# Module.net
KiCad netlist of a schematic drawn in Altium Designer
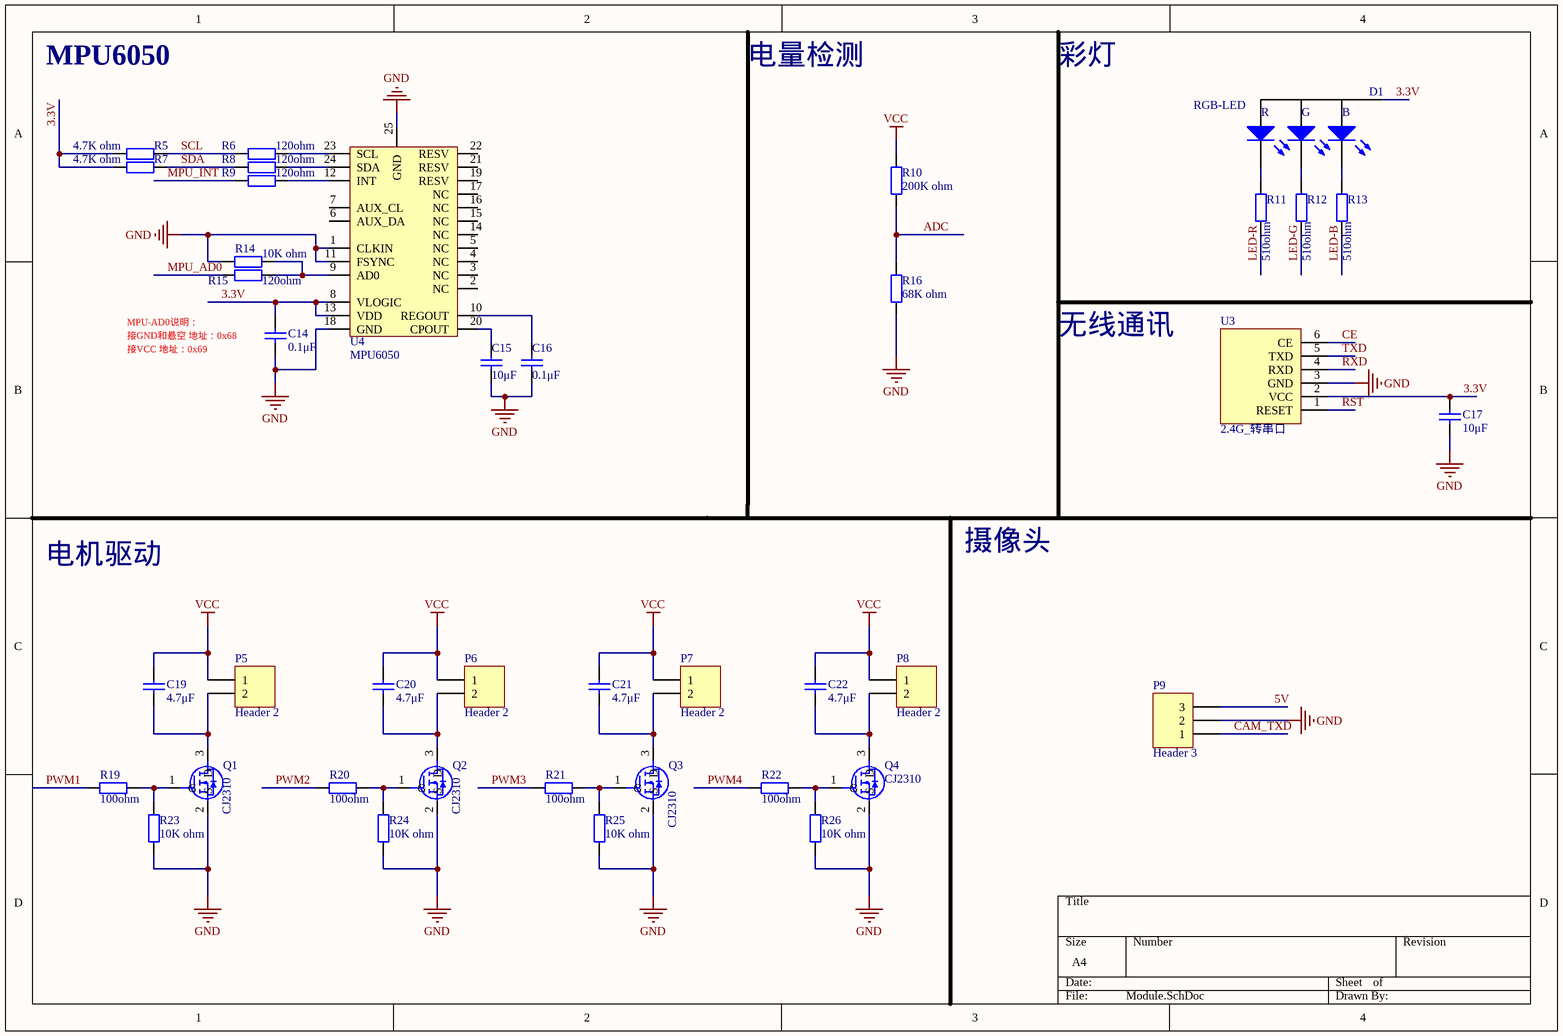
[diagram p0: Module.SchDoc]

(export (version "E")
  (design (tool "Eeschema 10.0.6"))
  (components
    (comp (ref "C14")
      (value "0.1μF")
      (footprint "0603C")
      (description "0.1μF_50V,X7R,±5%")
      (libsource (lib "Yang_Lib") (part "Cap_0.1μF_50V_0603"))
    )
    (comp (ref "C15")
      (value "10μF")
      (footprint "0603C")
      (description "10μF_35V,X5R,20%")
      (libsource (lib "Yang_Lib") (part "Cap_10μF_35V_0603"))
    )
    (comp (ref "C16")
      (value "0.1μF")
      (footprint "0603C")
      (description "0.1μF_50V,X7R,±5%")
      (libsource (lib "Yang_Lib") (part "Cap_0.1μF_50V_0603"))
    )
    (comp (ref "C17")
      (value "10μF")
      (footprint "0603C")
      (description "10μF_35V,X5R,20%")
      (libsource (lib "Yang_Lib") (part "Cap_10μF_35V_0603"))
    )
    (comp (ref "C19")
      (value "4.7μF")
      (footprint "0603C")
      (description "4.7μF_50V,±10%")
      (libsource (lib "Yang_Lib") (part "Cap_4.7μF_50V_0603"))
    )
    (comp (ref "C20")
      (value "4.7μF")
      (footprint "0603C")
      (description "4.7μF_50V,±10%")
      (libsource (lib "Yang_Lib") (part "Cap_4.7μF_50V_0603"))
    )
    (comp (ref "C21")
      (value "4.7μF")
      (footprint "0603C")
      (description "4.7μF_50V,±10%")
      (libsource (lib "Yang_Lib") (part "Cap_4.7μF_50V_0603"))
    )
    (comp (ref "C22")
      (value "4.7μF")
      (footprint "0603C")
      (description "4.7μF_50V,±10%")
      (libsource (lib "Yang_Lib") (part "Cap_4.7μF_50V_0603"))
    )
    (comp (ref "D1") (value "RGB-LED") (footprint "RGB-LED") (libsource (lib "Yang_Lib") (part "RGB-LED")))
    (comp (ref "P5")
      (value "Header 2")
      (footprint "HDR1X2")
      (description "Header, 2-Pin")
      (fields (field (name "PUBLISHER") "Altium Limited"))
      (libsource (lib "Miscellaneous Connectors") (part "Header 2"))
    )
    (comp (ref "P6")
      (value "Header 2")
      (footprint "HDR1X2")
      (description "Header, 2-Pin")
      (fields (field (name "PUBLISHER") "Altium Limited"))
      (libsource (lib "Miscellaneous Connectors") (part "Header 2"))
    )
    (comp (ref "P7")
      (value "Header 2")
      (footprint "HDR1X2")
      (description "Header, 2-Pin")
      (fields (field (name "PUBLISHER") "Altium Limited"))
      (libsource (lib "Miscellaneous Connectors") (part "Header 2"))
    )
    (comp (ref "P8")
      (value "Header 2")
      (footprint "HDR1X2")
      (description "Header, 2-Pin")
      (fields (field (name "PUBLISHER") "Altium Limited"))
      (libsource (lib "Miscellaneous Connectors") (part "Header 2"))
    )
    (comp (ref "P9")
      (value "Header 3")
      (footprint "HDR1X3")
      (description "Header, 3-Pin")
      (fields (field (name "PUBLISHER") "Altium Limited"))
      (libsource (lib "Miscellaneous Connectors") (part "Header 3"))
    )
    (comp (ref "Q1") (value "CJ2310") (footprint "SOT23-3") (libsource (lib "Yang_Lib") (part "CJ2310")))
    (comp (ref "Q2") (value "CJ2310") (footprint "SOT23-3") (libsource (lib "Yang_Lib") (part "CJ2310")))
    (comp (ref "Q3") (value "CJ2310") (footprint "SOT23-3") (libsource (lib "Yang_Lib") (part "CJ2310")))
    (comp (ref "Q4") (value "CJ2310") (footprint "SOT23-3") (libsource (lib "Yang_Lib") (part "CJ2310")))
    (comp (ref "R5")
      (value "4.7K ohm")
      (footprint "0603R")
      (description "4.7K ohm,1%")
      (libsource (lib "Yang_Lib") (part "Res_4.7K ohm_0603"))
    )
    (comp (ref "R6")
      (value "120ohm")
      (footprint "0603R")
      (description "120 ohm_5%")
      (libsource (lib "Yang_Lib") (part "Res_120ohm_0603"))
    )
    (comp (ref "R7")
      (value "4.7K ohm")
      (footprint "0603R")
      (description "4.7K ohm,1%")
      (libsource (lib "Yang_Lib") (part "Res_4.7K ohm_0603"))
    )
    (comp (ref "R8")
      (value "120ohm")
      (footprint "0603R")
      (description "120 ohm_5%")
      (libsource (lib "Yang_Lib") (part "Res_120ohm_0603"))
    )
    (comp (ref "R9")
      (value "120ohm")
      (footprint "0603R")
      (description "120 ohm_5%")
      (libsource (lib "Yang_Lib") (part "Res_120ohm_0603"))
    )
    (comp (ref "R10")
      (value "200K ohm")
      (footprint "0603R")
      (description "200K ohm,1%")
      (libsource (lib "Yang_Lib") (part "Res_200K ohm_0603"))
    )
    (comp (ref "R11")
      (value "510ohm")
      (footprint "0603R")
      (description "510 ohm,1%")
      (libsource (lib "Yang_Lib") (part "Res_510ohm_0603"))
    )
    (comp (ref "R12")
      (value "510ohm")
      (footprint "0603R")
      (description "510 ohm,1%")
      (libsource (lib "Yang_Lib") (part "Res_510ohm_0603"))
    )
    (comp (ref "R13")
      (value "510ohm")
      (footprint "0603R")
      (description "510 ohm,1%")
      (libsource (lib "Yang_Lib") (part "Res_510ohm_0603"))
    )
    (comp (ref "R14")
      (value "10K ohm")
      (footprint "0603R")
      (description "10K ohm,1%")
      (libsource (lib "") (part "Res_10K ohm_0603_1"))
    )
    (comp (ref "R15")
      (value "120ohm")
      (footprint "0603R")
      (description "120 ohm_5%")
      (libsource (lib "Yang_Lib") (part "Res_120ohm_0603"))
    )
    (comp (ref "R16")
      (value "68K ohm")
      (footprint "0603R")
      (description "68K ohm,1%")
      (libsource (lib "Yang_Lib") (part "Res_68K ohm_0603"))
    )
    (comp (ref "R19")
      (value "100ohm")
      (footprint "0603R")
      (description "100 ohm_5%")
      (libsource (lib "Yang_Lib") (part "Res_100ohm_0603"))
    )
    (comp (ref "R20")
      (value "100ohm")
      (footprint "0603R")
      (description "100 ohm_5%")
      (libsource (lib "Yang_Lib") (part "Res_100ohm_0603"))
    )
    (comp (ref "R21")
      (value "100ohm")
      (footprint "0603R")
      (description "100 ohm_5%")
      (libsource (lib "Yang_Lib") (part "Res_100ohm_0603"))
    )
    (comp (ref "R22")
      (value "100ohm")
      (footprint "0603R")
      (description "100 ohm_5%")
      (libsource (lib "Yang_Lib") (part "Res_100ohm_0603"))
    )
    (comp (ref "R23")
      (value "10K ohm")
      (footprint "0603R")
      (description "10K ohm,1%")
      (libsource (lib "Yang_Lib") (part "Res_10K ohm_0603"))
    )
    (comp (ref "R24")
      (value "10K ohm")
      (footprint "0603R")
      (description "10K ohm,1%")
      (libsource (lib "Yang_Lib") (part "Res_10K ohm_0603"))
    )
    (comp (ref "R25")
      (value "10K ohm")
      (footprint "0603R")
      (description "10K ohm,1%")
      (libsource (lib "Yang_Lib") (part "Res_10K ohm_0603"))
    )
    (comp (ref "R26")
      (value "10K ohm")
      (footprint "0603R")
      (description "10K ohm,1%")
      (libsource (lib "Yang_Lib") (part "Res_10K ohm_0603"))
    )
    (comp (ref "U3") (value "2.4G_转串口") (footprint "2.4G-串口") (libsource (lib "Yang_Lib") (part "2.4G_转串口")))
    (comp (ref "U4") (value "MPU6050") (footprint "QFN24") (libsource (lib "Yang_Lib") (part "MPU6050")))
  )
  (nets
    (net (code "1") (name "/3.3V") (class "Default")
      (node (ref "C14") (pin "2") (pinfunction "2_2") (pintype "passive"))
      (node (ref "C17") (pin "2") (pinfunction "2_2") (pintype "passive"))
      (node (ref "D1") (pin "3") (pinfunction "3_3") (pintype "passive"))
      (node (ref "R5") (pin "1") (pinfunction "1_1") (pintype "passive"))
      (node (ref "R7") (pin "1") (pinfunction "1_1") (pintype "passive"))
      (node (ref "U3") (pin "2") (pinfunction "VCC_2") (pintype "passive"))
      (node (ref "U4") (pin "13") (pinfunction "VDD_13") (pintype "passive"))
      (node (ref "U4") (pin "8") (pinfunction "VLOGIC_8") (pintype "passive"))
    )
    (net (code "2") (name "/5V") (class "Default")
      (node (ref "P9") (pin "3") (pinfunction "3_3") (pintype "passive"))
    )
    (net (code "3") (name "/ADC") (class "Default")
      (node (ref "R10") (pin "1") (pinfunction "1_1") (pintype "passive"))
      (node (ref "R16") (pin "2") (pinfunction "2_2") (pintype "passive"))
    )
    (net (code "4") (name "/CAM_TXD") (class "Default")
      (node (ref "P9") (pin "1") (pinfunction "1_1") (pintype "passive"))
    )
    (net (code "5") (name "/CE") (class "Default")
      (node (ref "U3") (pin "6") (pinfunction "CE_6") (pintype "passive"))
    )
    (net (code "6") (name "/LED-B") (class "Default")
      (node (ref "R13") (pin "1") (pinfunction "1_1") (pintype "passive"))
    )
    (net (code "7") (name "/LED-G") (class "Default")
      (node (ref "R12") (pin "1") (pinfunction "1_1") (pintype "passive"))
    )
    (net (code "8") (name "/LED-R") (class "Default")
      (node (ref "R11") (pin "1") (pinfunction "1_1") (pintype "passive"))
    )
    (net (code "9") (name "/MPU_AD0") (class "Default")
      (node (ref "R15") (pin "1") (pinfunction "1_1") (pintype "passive"))
    )
    (net (code "10") (name "/MPU_INT") (class "Default")
      (node (ref "R9") (pin "1") (pinfunction "1_1") (pintype "passive"))
    )
    (net (code "11") (name "/PWM1") (class "Default")
      (node (ref "R19") (pin "1") (pinfunction "1_1") (pintype "passive"))
    )
    (net (code "12") (name "/PWM2") (class "Default")
      (node (ref "R20") (pin "1") (pinfunction "1_1") (pintype "passive"))
    )
    (net (code "13") (name "/PWM3") (class "Default")
      (node (ref "R21") (pin "1") (pinfunction "1_1") (pintype "passive"))
    )
    (net (code "14") (name "/PWM4") (class "Default")
      (node (ref "R22") (pin "1") (pinfunction "1_1") (pintype "passive"))
    )
    (net (code "15") (name "/RST") (class "Default")
      (node (ref "U3") (pin "1") (pinfunction "RESET_1") (pintype "passive"))
    )
    (net (code "16") (name "/RXD") (class "Default")
      (node (ref "U3") (pin "4") (pinfunction "RXD_4") (pintype "passive"))
    )
    (net (code "17") (name "/SCL") (class "Default")
      (node (ref "R5") (pin "2") (pinfunction "2_2") (pintype "passive"))
      (node (ref "R6") (pin "1") (pinfunction "1_1") (pintype "passive"))
    )
    (net (code "18") (name "/SDA") (class "Default")
      (node (ref "R7") (pin "2") (pinfunction "2_2") (pintype "passive"))
      (node (ref "R8") (pin "1") (pinfunction "1_1") (pintype "passive"))
    )
    (net (code "19") (name "/TXD") (class "Default")
      (node (ref "U3") (pin "5") (pinfunction "TXD_5") (pintype "passive"))
    )
    (net (code "20") (name "GND") (class "Default")
      (node (ref "C14") (pin "1") (pinfunction "1_1") (pintype "passive"))
      (node (ref "C15") (pin "1") (pinfunction "1_1") (pintype "passive"))
      (node (ref "C16") (pin "1") (pinfunction "1_1") (pintype "passive"))
      (node (ref "C17") (pin "1") (pinfunction "1_1") (pintype "passive"))
      (node (ref "P9") (pin "2") (pinfunction "2_2") (pintype "passive"))
      (node (ref "Q1") (pin "2") (pinfunction "S_2") (pintype "passive"))
      (node (ref "Q2") (pin "2") (pinfunction "S_2") (pintype "passive"))
      (node (ref "Q3") (pin "2") (pinfunction "S_2") (pintype "passive"))
      (node (ref "Q4") (pin "2") (pinfunction "S_2") (pintype "passive"))
      (node (ref "R14") (pin "1") (pinfunction "1_1") (pintype "passive"))
      (node (ref "R16") (pin "1") (pinfunction "1_1") (pintype "passive"))
      (node (ref "R23") (pin "1") (pinfunction "1_1") (pintype "passive"))
      (node (ref "R24") (pin "1") (pinfunction "1_1") (pintype "passive"))
      (node (ref "R25") (pin "1") (pinfunction "1_1") (pintype "passive"))
      (node (ref "R26") (pin "1") (pinfunction "1_1") (pintype "passive"))
      (node (ref "U3") (pin "3") (pinfunction "GND_3") (pintype "passive"))
      (node (ref "U4") (pin "1") (pinfunction "CLKIN_1") (pintype "passive"))
      (node (ref "U4") (pin "11") (pinfunction "FSYNC_11") (pintype "passive"))
      (node (ref "U4") (pin "18") (pinfunction "GND_18") (pintype "passive"))
      (node (ref "U4") (pin "25") (pinfunction "GND_25") (pintype "passive"))
    )
    (net (code "21") (name "Net-(D1-Pad1)") (class "Default")
      (node (ref "D1") (pin "1") (pinfunction "1_1") (pintype "passive"))
      (node (ref "R13") (pin "2") (pinfunction "2_2") (pintype "passive"))
    )
    (net (code "22") (name "Net-(D1-Pad2)") (class "Default")
      (node (ref "D1") (pin "2") (pinfunction "2_2") (pintype "passive"))
      (node (ref "R12") (pin "2") (pinfunction "2_2") (pintype "passive"))
    )
    (net (code "23") (name "Net-(D1-Pad4)") (class "Default")
      (node (ref "D1") (pin "4") (pinfunction "4_4") (pintype "passive"))
      (node (ref "R11") (pin "2") (pinfunction "2_2") (pintype "passive"))
    )
    (net (code "24") (name "Net-(Q1-D)") (class "Default")
      (node (ref "C19") (pin "1") (pinfunction "1_1") (pintype "passive"))
      (node (ref "P5") (pin "2") (pinfunction "2_2") (pintype "passive"))
      (node (ref "Q1") (pin "3") (pinfunction "D_3") (pintype "passive"))
    )
    (net (code "25") (name "Net-(Q1-G)") (class "Default")
      (node (ref "Q1") (pin "1") (pinfunction "G_1") (pintype "passive"))
      (node (ref "R19") (pin "2") (pinfunction "2_2") (pintype "passive"))
      (node (ref "R23") (pin "2") (pinfunction "2_2") (pintype "passive"))
    )
    (net (code "26") (name "Net-(Q2-D)") (class "Default")
      (node (ref "C20") (pin "1") (pinfunction "1_1") (pintype "passive"))
      (node (ref "P6") (pin "2") (pinfunction "2_2") (pintype "passive"))
      (node (ref "Q2") (pin "3") (pinfunction "D_3") (pintype "passive"))
    )
    (net (code "27") (name "Net-(Q2-G)") (class "Default")
      (node (ref "Q2") (pin "1") (pinfunction "G_1") (pintype "passive"))
      (node (ref "R20") (pin "2") (pinfunction "2_2") (pintype "passive"))
      (node (ref "R24") (pin "2") (pinfunction "2_2") (pintype "passive"))
    )
    (net (code "28") (name "Net-(Q3-D)") (class "Default")
      (node (ref "C21") (pin "1") (pinfunction "1_1") (pintype "passive"))
      (node (ref "P7") (pin "2") (pinfunction "2_2") (pintype "passive"))
      (node (ref "Q3") (pin "3") (pinfunction "D_3") (pintype "passive"))
    )
    (net (code "29") (name "Net-(Q3-G)") (class "Default")
      (node (ref "Q3") (pin "1") (pinfunction "G_1") (pintype "passive"))
      (node (ref "R21") (pin "2") (pinfunction "2_2") (pintype "passive"))
      (node (ref "R25") (pin "2") (pinfunction "2_2") (pintype "passive"))
    )
    (net (code "30") (name "Net-(Q4-D)") (class "Default")
      (node (ref "C22") (pin "1") (pinfunction "1_1") (pintype "passive"))
      (node (ref "P8") (pin "2") (pinfunction "2_2") (pintype "passive"))
      (node (ref "Q4") (pin "3") (pinfunction "D_3") (pintype "passive"))
    )
    (net (code "31") (name "Net-(Q4-G)") (class "Default")
      (node (ref "Q4") (pin "1") (pinfunction "G_1") (pintype "passive"))
      (node (ref "R22") (pin "2") (pinfunction "2_2") (pintype "passive"))
      (node (ref "R26") (pin "2") (pinfunction "2_2") (pintype "passive"))
    )
    (net (code "32") (name "Net-(U4-AD0)") (class "Default")
      (node (ref "R14") (pin "2") (pinfunction "2_2") (pintype "passive"))
      (node (ref "R15") (pin "2") (pinfunction "2_2") (pintype "passive"))
      (node (ref "U4") (pin "9") (pinfunction "AD0_9") (pintype "passive"))
    )
    (net (code "33") (name "Net-(U4-CPOUT)") (class "Default")
      (node (ref "C15") (pin "2") (pinfunction "2_2") (pintype "passive"))
      (node (ref "U4") (pin "20") (pinfunction "CPOUT_20") (pintype "passive"))
    )
    (net (code "34") (name "Net-(U4-INT)") (class "Default")
      (node (ref "R9") (pin "2") (pinfunction "2_2") (pintype "passive"))
      (node (ref "U4") (pin "12") (pinfunction "INT_12") (pintype "passive"))
    )
    (net (code "35") (name "Net-(U4-REGOUT)") (class "Default")
      (node (ref "C16") (pin "2") (pinfunction "2_2") (pintype "passive"))
      (node (ref "U4") (pin "10") (pinfunction "REGOUT_10") (pintype "passive"))
    )
    (net (code "36") (name "Net-(U4-SCL)") (class "Default")
      (node (ref "R6") (pin "2") (pinfunction "2_2") (pintype "passive"))
      (node (ref "U4") (pin "23") (pinfunction "SCL_23") (pintype "passive"))
    )
    (net (code "37") (name "Net-(U4-SDA)") (class "Default")
      (node (ref "R8") (pin "2") (pinfunction "2_2") (pintype "passive"))
      (node (ref "U4") (pin "24") (pinfunction "SDA_24") (pintype "passive"))
    )
    (net (code "38") (name "VCC") (class "Default")
      (node (ref "C19") (pin "2") (pinfunction "2_2") (pintype "passive"))
      (node (ref "C20") (pin "2") (pinfunction "2_2") (pintype "passive"))
      (node (ref "C21") (pin "2") (pinfunction "2_2") (pintype "passive"))
      (node (ref "C22") (pin "2") (pinfunction "2_2") (pintype "passive"))
      (node (ref "P5") (pin "1") (pinfunction "1_1") (pintype "passive"))
      (node (ref "P6") (pin "1") (pinfunction "1_1") (pintype "passive"))
      (node (ref "P7") (pin "1") (pinfunction "1_1") (pintype "passive"))
      (node (ref "P8") (pin "1") (pinfunction "1_1") (pintype "passive"))
      (node (ref "R10") (pin "2") (pinfunction "2_2") (pintype "passive"))
    )
    (net (code "39") (name "unconnected-(U4-AUX_CL-Pad7)") (class "Default")
      (node (ref "U4") (pin "7") (pinfunction "AUX_CL_7") (pintype "passive"))
    )
    (net (code "40") (name "unconnected-(U4-AUX_DA-Pad6)") (class "Default")
      (node (ref "U4") (pin "6") (pinfunction "AUX_DA_6") (pintype "passive"))
    )
    (net (code "41") (name "unconnected-(U4-NC-Pad2)") (class "Default")
      (node (ref "U4") (pin "2") (pinfunction "NC_2") (pintype "passive"))
    )
    (net (code "42") (name "unconnected-(U4-NC-Pad3)") (class "Default")
      (node (ref "U4") (pin "3") (pinfunction "NC_3") (pintype "passive"))
    )
    (net (code "43") (name "unconnected-(U4-NC-Pad4)") (class "Default")
      (node (ref "U4") (pin "4") (pinfunction "NC_4") (pintype "passive"))
    )
    (net (code "44") (name "unconnected-(U4-NC-Pad5)") (class "Default")
      (node (ref "U4") (pin "5") (pinfunction "NC_5") (pintype "passive"))
    )
    (net (code "45") (name "unconnected-(U4-NC-Pad14)") (class "Default")
      (node (ref "U4") (pin "14") (pinfunction "NC_14") (pintype "passive"))
    )
    (net (code "46") (name "unconnected-(U4-NC-Pad15)") (class "Default")
      (node (ref "U4") (pin "15") (pinfunction "NC_15") (pintype "passive"))
    )
    (net (code "47") (name "unconnected-(U4-NC-Pad16)") (class "Default")
      (node (ref "U4") (pin "16") (pinfunction "NC_16") (pintype "passive"))
    )
    (net (code "48") (name "unconnected-(U4-NC-Pad17)") (class "Default")
      (node (ref "U4") (pin "17") (pinfunction "NC_17") (pintype "passive"))
    )
    (net (code "49") (name "unconnected-(U4-RESV-Pad19)") (class "Default")
      (node (ref "U4") (pin "19") (pinfunction "RESV_19") (pintype "passive"))
    )
    (net (code "50") (name "unconnected-(U4-RESV-Pad21)") (class "Default")
      (node (ref "U4") (pin "21") (pinfunction "RESV_21") (pintype "passive"))
    )
    (net (code "51") (name "unconnected-(U4-RESV-Pad22)") (class "Default")
      (node (ref "U4") (pin "22") (pinfunction "RESV_22") (pintype "passive"))
    )
  )
)
